# TI_Bluetooth.net
KiCad netlist of a schematic drawn in EAGLE
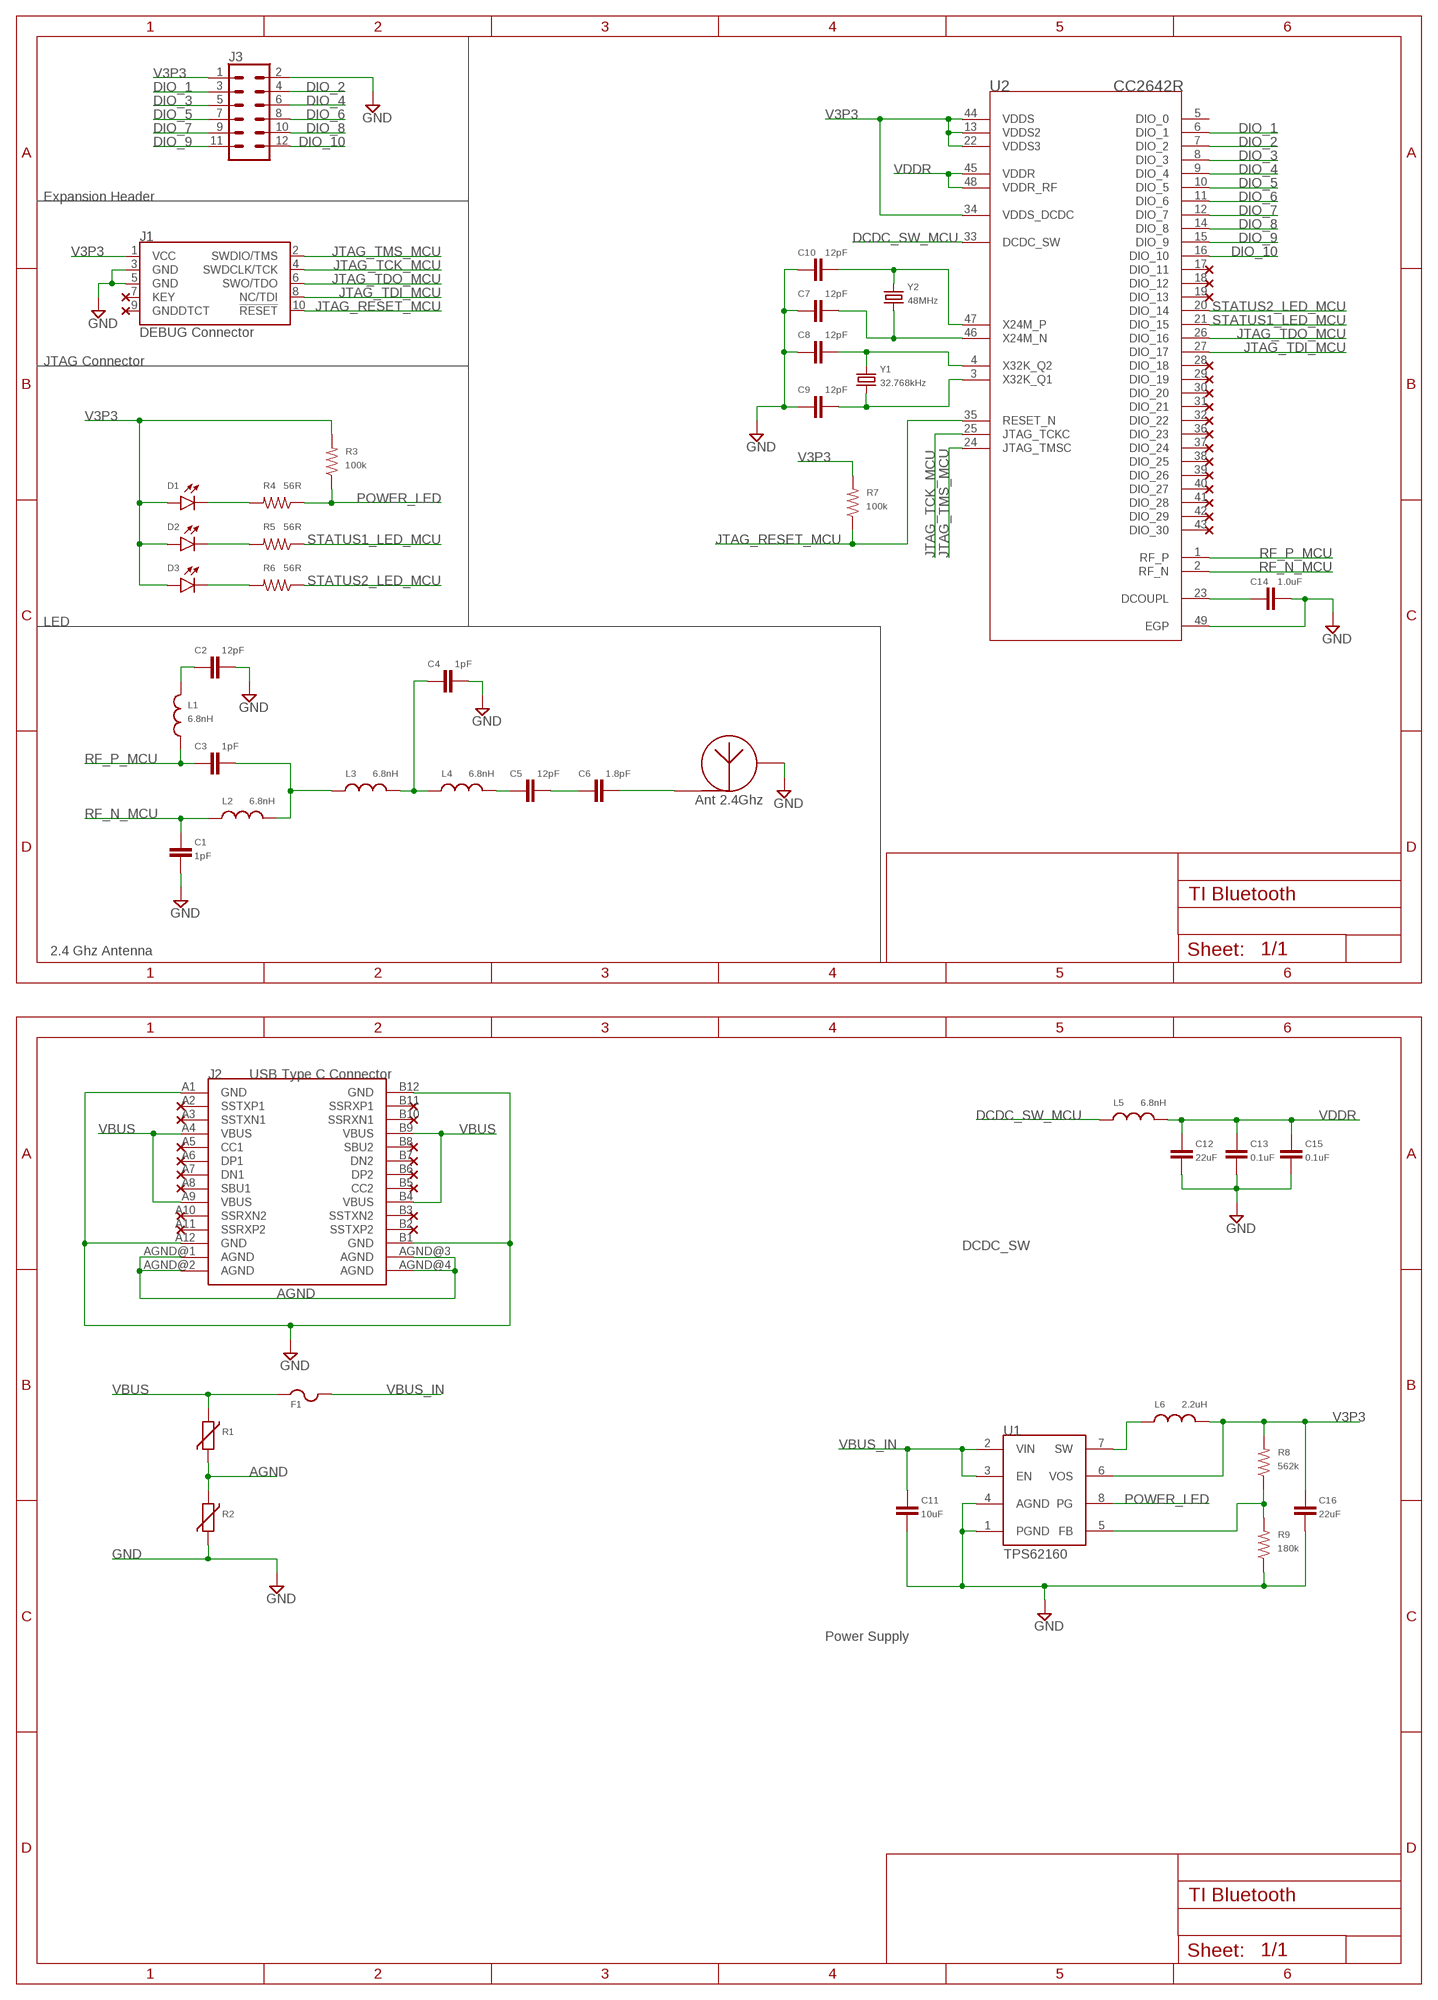
[diagram p0: schematic, sheet 1]

(export (version "E")
  (design (tool "Eeschema 10.0.6"))
  (components
    (comp (ref "ANT1")
      (value "TI_AN043")
      (footprint "eagle-import:TI_AN043")
      (libsource (lib "eagle-import") (part "TI_AN043"))
    )
    (comp (ref "C1")
      (value "1pF")
      (footprint "eagle-import:C0603")
      (libsource (lib "eagle-import") (part "C-EUC0603"))
    )
    (comp (ref "C2")
      (value "12pF")
      (footprint "eagle-import:C0603")
      (libsource (lib "eagle-import") (part "C-EUC0603"))
    )
    (comp (ref "C3")
      (value "1pF")
      (footprint "eagle-import:C0603")
      (libsource (lib "eagle-import") (part "C-EUC0603"))
    )
    (comp (ref "C4")
      (value "1pF")
      (footprint "eagle-import:C0603")
      (libsource (lib "eagle-import") (part "C-EUC0603"))
    )
    (comp (ref "C5")
      (value "12pF")
      (footprint "eagle-import:C0603")
      (libsource (lib "eagle-import") (part "C-EUC0603"))
    )
    (comp (ref "C6")
      (value "1.8pF")
      (footprint "eagle-import:C0603")
      (libsource (lib "eagle-import") (part "C-EUC0603"))
    )
    (comp (ref "C7")
      (value "12pF")
      (footprint "eagle-import:C0603")
      (libsource (lib "eagle-import") (part "C-EUC0603"))
    )
    (comp (ref "C8")
      (value "12pF")
      (footprint "eagle-import:C0603")
      (libsource (lib "eagle-import") (part "C-EUC0603"))
    )
    (comp (ref "C9")
      (value "12pF")
      (footprint "eagle-import:C0603")
      (libsource (lib "eagle-import") (part "C-EUC0603"))
    )
    (comp (ref "C10")
      (value "12pF")
      (footprint "eagle-import:C0603")
      (libsource (lib "eagle-import") (part "C-EUC0603"))
    )
    (comp (ref "C11")
      (value "10uF")
      (footprint "eagle-import:C0603")
      (libsource (lib "eagle-import") (part "C-EUC0603"))
    )
    (comp (ref "C12")
      (value "22uF")
      (footprint "eagle-import:C0603")
      (libsource (lib "eagle-import") (part "C-EUC0603"))
    )
    (comp (ref "C13")
      (value "0.1uF")
      (footprint "eagle-import:C0603")
      (libsource (lib "eagle-import") (part "C-EUC0603"))
    )
    (comp (ref "C14")
      (value "1.0uF")
      (footprint "eagle-import:C0603")
      (libsource (lib "eagle-import") (part "C-EUC0603"))
    )
    (comp (ref "C15")
      (value "0.1uF")
      (footprint "eagle-import:C0603")
      (libsource (lib "eagle-import") (part "C-EUC0603"))
    )
    (comp (ref "C16")
      (value "22uF")
      (footprint "eagle-import:C0603")
      (libsource (lib "eagle-import") (part "C-EUC0603"))
    )
    (comp (ref "D1")
      (value "POWER")
      (footprint "eagle-import:LED-1206")
      (libsource (lib "eagle-import") (part "LED1206"))
    )
    (comp (ref "D2")
      (value "STATUS1")
      (footprint "eagle-import:LED-1206")
      (libsource (lib "eagle-import") (part "LED1206"))
    )
    (comp (ref "D3")
      (value "STATUS2")
      (footprint "eagle-import:LED-1206")
      (libsource (lib "eagle-import") (part "LED1206"))
    )
    (comp (ref "F1")
      (value "1206L110THYR")
      (footprint "eagle-import:R1206")
      (libsource (lib "eagle-import") (part "PTCFUSE-1206"))
    )
    (comp (ref "J1")
      (value "DEBUG Connector")
      (footprint "eagle-import:SAMTECH_FTSH-105-01")
      (libsource (lib "eagle-import") (part "CORTEX_DEBUG_SMD"))
    )
    (comp (ref "J2")
      (value "USB Type C Connector")
      (footprint "eagle-import:USB-C31-S-RA-CS1-BK-TR")
      (libsource (lib "eagle-import") (part "USB-C31-S-RA-CS1-BK-TR"))
    )
    (comp (ref "J3")
      (value "Expansion Header")
      (footprint "eagle-import:2X6")
      (libsource (lib "eagle-import") (part "CONN_06X2PTH_FEMALE"))
    )
    (comp (ref "L1")
      (value "6.8nH")
      (footprint "eagle-import:INDC1608X95N")
      (libsource (lib "eagle-import") (part "LCHIP-0603(1608-METRIC)_"))
    )
    (comp (ref "L2")
      (value "6.8nH")
      (footprint "eagle-import:INDC1608X95N")
      (libsource (lib "eagle-import") (part "LCHIP-0603(1608-METRIC)_"))
    )
    (comp (ref "L3")
      (value "6.8nH")
      (footprint "eagle-import:INDC1608X95N")
      (libsource (lib "eagle-import") (part "LCHIP-0603(1608-METRIC)_"))
    )
    (comp (ref "L4")
      (value "6.8nH")
      (footprint "eagle-import:INDC1608X95N")
      (libsource (lib "eagle-import") (part "LCHIP-0603(1608-METRIC)_"))
    )
    (comp (ref "L5")
      (value "6.8nH")
      (footprint "eagle-import:INDC1608X95N")
      (libsource (lib "eagle-import") (part "LCHIP-0603(1608-METRIC)_"))
    )
    (comp (ref "L6")
      (value "2.2uH")
      (footprint "eagle-import:INDC1608X95N")
      (libsource (lib "eagle-import") (part "LCHIP-0603(1608-METRIC)_"))
    )
    (comp (ref "R1")
      (value "V5.5MLA")
      (footprint "eagle-import:CT_CN0603")
      (libsource (lib "eagle-import") (part "VARISTORCN0603"))
    )
    (comp (ref "R2")
      (value "V5.5MLA")
      (footprint "eagle-import:CT_CN0603")
      (libsource (lib "eagle-import") (part "VARISTORCN0603"))
    )
    (comp (ref "R3")
      (value "100k")
      (footprint "eagle-import:R0603")
      (libsource (lib "eagle-import") (part "R-US_R0603"))
    )
    (comp (ref "R4")
      (value "56R")
      (footprint "eagle-import:R0603")
      (libsource (lib "eagle-import") (part "R-US_R0603"))
    )
    (comp (ref "R5")
      (value "56R")
      (footprint "eagle-import:R0603")
      (libsource (lib "eagle-import") (part "R-US_R0603"))
    )
    (comp (ref "R6")
      (value "56R")
      (footprint "eagle-import:R0603")
      (libsource (lib "eagle-import") (part "R-US_R0603"))
    )
    (comp (ref "R7")
      (value "100k")
      (footprint "eagle-import:R0603")
      (libsource (lib "eagle-import") (part "R-US_R0603"))
    )
    (comp (ref "R8")
      (value "562k")
      (footprint "eagle-import:R0603")
      (libsource (lib "eagle-import") (part "R-US_R0603"))
    )
    (comp (ref "R9")
      (value "180k")
      (footprint "eagle-import:R0603")
      (libsource (lib "eagle-import") (part "R-US_R0603"))
    )
    (comp (ref "U1")
      (value "TPS62160")
      (footprint "eagle-import:SOP65P490X110-8N")
      (libsource (lib "eagle-import") (part "TPS62160VSSOP"))
    )
    (comp (ref "U2")
      (value "CC2642R")
      (footprint "eagle-import:QFN50P700X690X100-49T515N")
      (libsource (lib "eagle-import") (part "CC2642R1FRGZRRGZ0048A"))
    )
    (comp (ref "Y1")
      (value "32.768kHz")
      (footprint "eagle-import:CRYSTAL-PTH-2X6-CYL")
      (libsource (lib "eagle-import") (part "CRYSTAL-32.768KHZPTH-2X6"))
    )
    (comp (ref "Y2")
      (value "48MHz")
      (footprint "eagle-import:CRYSTAL-SMD-5X3.2-2PAD")
      (libsource (lib "eagle-import") (part "CRYSTALSMD-5X3.2-2PAD"))
    )
  )
  (nets
    (net (code "1") (name "/AGND") (class "Default")
      (node (ref "J2") (pin "AGND@1") (pinfunction "AGND_AGND@1") (pintype "bidirectional"))
      (node (ref "J2") (pin "AGND@2") (pinfunction "AGND_AGND@2") (pintype "bidirectional"))
      (node (ref "J2") (pin "AGND@3") (pinfunction "AGND_AGND@3") (pintype "bidirectional"))
      (node (ref "J2") (pin "AGND@4") (pinfunction "AGND_AGND@4") (pintype "bidirectional"))
      (node (ref "R1") (pin "2") (pinfunction "2_2") (pintype "passive"))
      (node (ref "R2") (pin "1") (pinfunction "1_1") (pintype "passive"))
    )
    (net (code "2") (name "/DCDC_SW_MCU") (class "Default")
      (node (ref "L5") (pin "1") (pinfunction "1_1") (pintype "passive"))
      (node (ref "U2") (pin "33") (pinfunction "DCDC_SW_33") (pintype "power_in"))
    )
    (net (code "3") (name "/DIO_1") (class "Default")
      (node (ref "J3") (pin "3") (pinfunction "3_3") (pintype "passive"))
      (node (ref "U2") (pin "6") (pinfunction "DIO_1_6") (pintype "bidirectional"))
    )
    (net (code "4") (name "/DIO_2") (class "Default")
      (node (ref "J3") (pin "4") (pinfunction "4_4") (pintype "passive"))
      (node (ref "U2") (pin "7") (pinfunction "DIO_2_7") (pintype "bidirectional"))
    )
    (net (code "5") (name "/DIO_3") (class "Default")
      (node (ref "J3") (pin "5") (pinfunction "5_5") (pintype "passive"))
      (node (ref "U2") (pin "8") (pinfunction "DIO_3_8") (pintype "bidirectional"))
    )
    (net (code "6") (name "/DIO_4") (class "Default")
      (node (ref "J3") (pin "6") (pinfunction "6_6") (pintype "passive"))
      (node (ref "U2") (pin "9") (pinfunction "DIO_4_9") (pintype "bidirectional"))
    )
    (net (code "7") (name "/DIO_5") (class "Default")
      (node (ref "J3") (pin "7") (pinfunction "7_7") (pintype "passive"))
      (node (ref "U2") (pin "10") (pinfunction "DIO_5_10") (pintype "bidirectional"))
    )
    (net (code "8") (name "/DIO_6") (class "Default")
      (node (ref "J3") (pin "8") (pinfunction "8_8") (pintype "passive"))
      (node (ref "U2") (pin "11") (pinfunction "DIO_6_11") (pintype "bidirectional"))
    )
    (net (code "9") (name "/DIO_7") (class "Default")
      (node (ref "J3") (pin "9") (pinfunction "9_9") (pintype "passive"))
      (node (ref "U2") (pin "12") (pinfunction "DIO_7_12") (pintype "bidirectional"))
    )
    (net (code "10") (name "/DIO_8") (class "Default")
      (node (ref "J3") (pin "10") (pinfunction "10_10") (pintype "passive"))
      (node (ref "U2") (pin "14") (pinfunction "DIO_8_14") (pintype "bidirectional"))
    )
    (net (code "11") (name "/DIO_9") (class "Default")
      (node (ref "J3") (pin "11") (pinfunction "11_11") (pintype "passive"))
      (node (ref "U2") (pin "15") (pinfunction "DIO_9_15") (pintype "bidirectional"))
    )
    (net (code "12") (name "/DIO_10") (class "Default")
      (node (ref "J3") (pin "12") (pinfunction "12_12") (pintype "passive"))
      (node (ref "U2") (pin "16") (pinfunction "DIO_10_16") (pintype "bidirectional"))
    )
    (net (code "13") (name "/JTAG_RESET_MCU") (class "Default")
      (node (ref "J1") (pin "10") (pinfunction "~{RESET}_10") (pintype "bidirectional"))
      (node (ref "R7") (pin "1") (pinfunction "1_1") (pintype "passive"))
      (node (ref "U2") (pin "35") (pinfunction "RESET_N_35") (pintype "input"))
    )
    (net (code "14") (name "/JTAG_TCK_MCU") (class "Default")
      (node (ref "J1") (pin "4") (pinfunction "SWDCLK/TCK_4") (pintype "bidirectional"))
      (node (ref "U2") (pin "25") (pinfunction "JTAG_TCKC_25") (pintype "bidirectional"))
    )
    (net (code "15") (name "/JTAG_TDI_MCU") (class "Default")
      (node (ref "J1") (pin "8") (pinfunction "NC/TDI_8") (pintype "bidirectional"))
      (node (ref "U2") (pin "27") (pinfunction "DIO_17_27") (pintype "bidirectional"))
    )
    (net (code "16") (name "/JTAG_TDO_MCU") (class "Default")
      (node (ref "J1") (pin "6") (pinfunction "SWO/TDO_6") (pintype "bidirectional"))
      (node (ref "U2") (pin "26") (pinfunction "DIO_16_26") (pintype "bidirectional"))
    )
    (net (code "17") (name "/JTAG_TMS_MCU") (class "Default")
      (node (ref "J1") (pin "2") (pinfunction "SWDIO/TMS_2") (pintype "bidirectional"))
      (node (ref "U2") (pin "24") (pinfunction "JTAG_TMSC_24") (pintype "bidirectional"))
    )
    (net (code "18") (name "/POWER_LED") (class "Default")
      (node (ref "R3") (pin "1") (pinfunction "1_1") (pintype "passive"))
      (node (ref "R4") (pin "1") (pinfunction "1_1") (pintype "passive"))
      (node (ref "U1") (pin "8") (pinfunction "PG_8") (pintype "bidirectional"))
    )
    (net (code "19") (name "/RF_N_MCU") (class "Default")
      (node (ref "C1") (pin "1") (pinfunction "1_1") (pintype "passive"))
      (node (ref "L2") (pin "1") (pinfunction "1_1") (pintype "passive"))
      (node (ref "U2") (pin "2") (pinfunction "RF_N_2") (pintype "bidirectional"))
    )
    (net (code "20") (name "/RF_P_MCU") (class "Default")
      (node (ref "C3") (pin "1") (pinfunction "1_1") (pintype "passive"))
      (node (ref "L1") (pin "1") (pinfunction "1_1") (pintype "passive"))
      (node (ref "U2") (pin "1") (pinfunction "RF_P_1") (pintype "bidirectional"))
    )
    (net (code "21") (name "/STATUS1_LED_MCU") (class "Default")
      (node (ref "R5") (pin "1") (pinfunction "1_1") (pintype "passive"))
      (node (ref "U2") (pin "21") (pinfunction "DIO_15_21") (pintype "bidirectional"))
    )
    (net (code "22") (name "/STATUS2_LED_MCU") (class "Default")
      (node (ref "R6") (pin "1") (pinfunction "1_1") (pintype "passive"))
      (node (ref "U2") (pin "20") (pinfunction "DIO_14_20") (pintype "bidirectional"))
    )
    (net (code "23") (name "/V3P3") (class "Default")
      (node (ref "C16") (pin "1") (pinfunction "1_1") (pintype "passive"))
      (node (ref "D1") (pin "A") (pinfunction "A_A") (pintype "passive"))
      (node (ref "D2") (pin "A") (pinfunction "A_A") (pintype "passive"))
      (node (ref "D3") (pin "A") (pinfunction "A_A") (pintype "passive"))
      (node (ref "J1") (pin "1") (pinfunction "VCC_1") (pintype "bidirectional"))
      (node (ref "J3") (pin "1") (pinfunction "1_1") (pintype "passive"))
      (node (ref "L6") (pin "2") (pinfunction "2_2") (pintype "passive"))
      (node (ref "R3") (pin "2") (pinfunction "2_2") (pintype "passive"))
      (node (ref "R7") (pin "2") (pinfunction "2_2") (pintype "passive"))
      (node (ref "R8") (pin "2") (pinfunction "2_2") (pintype "passive"))
      (node (ref "U1") (pin "6") (pinfunction "VOS_6") (pintype "bidirectional"))
      (node (ref "U2") (pin "13") (pinfunction "VDDS2_13") (pintype "power_in"))
      (node (ref "U2") (pin "22") (pinfunction "VDDS3_22") (pintype "power_in"))
      (node (ref "U2") (pin "34") (pinfunction "VDDS_DCDC_34") (pintype "power_in"))
      (node (ref "U2") (pin "44") (pinfunction "VDDS_44") (pintype "power_in"))
    )
    (net (code "24") (name "/VBUS") (class "Default")
      (node (ref "F1") (pin "1") (pinfunction "1_1") (pintype "passive"))
      (node (ref "J2") (pin "A4") (pinfunction "VBUS_A4") (pintype "bidirectional"))
      (node (ref "J2") (pin "A9") (pinfunction "VBUS_A9") (pintype "bidirectional"))
      (node (ref "J2") (pin "B4") (pinfunction "VBUS_B4") (pintype "bidirectional"))
      (node (ref "J2") (pin "B9") (pinfunction "VBUS_B9") (pintype "bidirectional"))
      (node (ref "R1") (pin "1") (pinfunction "1_1") (pintype "passive"))
    )
    (net (code "25") (name "/VBUS_IN") (class "Default")
      (node (ref "C11") (pin "1") (pinfunction "1_1") (pintype "passive"))
      (node (ref "F1") (pin "2") (pinfunction "2_2") (pintype "passive"))
      (node (ref "U1") (pin "2") (pinfunction "VIN_2") (pintype "bidirectional"))
      (node (ref "U1") (pin "3") (pinfunction "EN_3") (pintype "bidirectional"))
    )
    (net (code "26") (name "/VDDR") (class "Default")
      (node (ref "C12") (pin "1") (pinfunction "1_1") (pintype "passive"))
      (node (ref "C13") (pin "1") (pinfunction "1_1") (pintype "passive"))
      (node (ref "C15") (pin "1") (pinfunction "1_1") (pintype "passive"))
      (node (ref "L5") (pin "2") (pinfunction "2_2") (pintype "passive"))
      (node (ref "U2") (pin "45") (pinfunction "VDDR_45") (pintype "power_in"))
      (node (ref "U2") (pin "48") (pinfunction "VDDR_RF_48") (pintype "power_in"))
    )
    (net (code "27") (name "GND") (class "Default")
      (node (ref "ANT1") (pin "FEED") (pinfunction "FEED_FEED") (pintype "bidirectional"))
      (node (ref "ANT1") (pin "RETURN") (pinfunction "RETURN_RETURN") (pintype "bidirectional"))
      (node (ref "C1") (pin "2") (pinfunction "2_2") (pintype "passive"))
      (node (ref "C10") (pin "2") (pinfunction "2_2") (pintype "passive"))
      (node (ref "C11") (pin "2") (pinfunction "2_2") (pintype "passive"))
      (node (ref "C12") (pin "2") (pinfunction "2_2") (pintype "passive"))
      (node (ref "C13") (pin "2") (pinfunction "2_2") (pintype "passive"))
      (node (ref "C14") (pin "2") (pinfunction "2_2") (pintype "passive"))
      (node (ref "C15") (pin "2") (pinfunction "2_2") (pintype "passive"))
      (node (ref "C16") (pin "2") (pinfunction "2_2") (pintype "passive"))
      (node (ref "C2") (pin "2") (pinfunction "2_2") (pintype "passive"))
      (node (ref "C4") (pin "2") (pinfunction "2_2") (pintype "passive"))
      (node (ref "C6") (pin "2") (pinfunction "2_2") (pintype "passive"))
      (node (ref "C7") (pin "1") (pinfunction "1_1") (pintype "passive"))
      (node (ref "C8") (pin "1") (pinfunction "1_1") (pintype "passive"))
      (node (ref "C9") (pin "1") (pinfunction "1_1") (pintype "passive"))
      (node (ref "J1") (pin "3") (pinfunction "GND_3") (pintype "bidirectional"))
      (node (ref "J1") (pin "5") (pinfunction "GND_5") (pintype "bidirectional"))
      (node (ref "J2") (pin "A1") (pinfunction "GND_A1") (pintype "bidirectional"))
      (node (ref "J2") (pin "A12") (pinfunction "GND_A12") (pintype "bidirectional"))
      (node (ref "J2") (pin "B1") (pinfunction "GND_B1") (pintype "bidirectional"))
      (node (ref "J2") (pin "B12") (pinfunction "GND_B12") (pintype "bidirectional"))
      (node (ref "J3") (pin "2") (pinfunction "2_2") (pintype "passive"))
      (node (ref "R2") (pin "2") (pinfunction "2_2") (pintype "passive"))
      (node (ref "R9") (pin "1") (pinfunction "1_1") (pintype "passive"))
      (node (ref "U1") (pin "1") (pinfunction "PGND_1") (pintype "bidirectional"))
      (node (ref "U1") (pin "4") (pinfunction "AGND_4") (pintype "bidirectional"))
      (node (ref "U2") (pin "49") (pinfunction "EGP_49") (pintype "power_in"))
    )
    (net (code "28") (name "Net-(C2-Pad1)") (class "Default")
      (node (ref "C2") (pin "1") (pinfunction "1_1") (pintype "passive"))
      (node (ref "L1") (pin "2") (pinfunction "2_2") (pintype "passive"))
    )
    (net (code "29") (name "Net-(C3-Pad2)") (class "Default")
      (node (ref "C3") (pin "2") (pinfunction "2_2") (pintype "passive"))
      (node (ref "L2") (pin "2") (pinfunction "2_2") (pintype "passive"))
      (node (ref "L3") (pin "1") (pinfunction "1_1") (pintype "passive"))
    )
    (net (code "30") (name "Net-(C4-Pad1)") (class "Default")
      (node (ref "C4") (pin "1") (pinfunction "1_1") (pintype "passive"))
      (node (ref "L3") (pin "2") (pinfunction "2_2") (pintype "passive"))
      (node (ref "L4") (pin "1") (pinfunction "1_1") (pintype "passive"))
    )
    (net (code "31") (name "Net-(C5-Pad1)") (class "Default")
      (node (ref "C5") (pin "1") (pinfunction "1_1") (pintype "passive"))
      (node (ref "L4") (pin "2") (pinfunction "2_2") (pintype "passive"))
    )
    (net (code "32") (name "Net-(C5-Pad2)") (class "Default")
      (node (ref "C5") (pin "2") (pinfunction "2_2") (pintype "passive"))
      (node (ref "C6") (pin "1") (pinfunction "1_1") (pintype "passive"))
    )
    (net (code "33") (name "Net-(D1-PadC)") (class "Default")
      (node (ref "D1") (pin "C") (pinfunction "C_C") (pintype "passive"))
      (node (ref "R4") (pin "2") (pinfunction "2_2") (pintype "passive"))
    )
    (net (code "34") (name "Net-(D2-PadC)") (class "Default")
      (node (ref "D2") (pin "C") (pinfunction "C_C") (pintype "passive"))
      (node (ref "R5") (pin "2") (pinfunction "2_2") (pintype "passive"))
    )
    (net (code "35") (name "Net-(D3-PadC)") (class "Default")
      (node (ref "D3") (pin "C") (pinfunction "C_C") (pintype "passive"))
      (node (ref "R6") (pin "2") (pinfunction "2_2") (pintype "passive"))
    )
    (net (code "36") (name "Net-(U1-FB)") (class "Default")
      (node (ref "R8") (pin "1") (pinfunction "1_1") (pintype "passive"))
      (node (ref "R9") (pin "2") (pinfunction "2_2") (pintype "passive"))
      (node (ref "U1") (pin "5") (pinfunction "FB_5") (pintype "bidirectional"))
    )
    (net (code "37") (name "Net-(U1-SW)") (class "Default")
      (node (ref "L6") (pin "1") (pinfunction "1_1") (pintype "passive"))
      (node (ref "U1") (pin "7") (pinfunction "SW_7") (pintype "bidirectional"))
    )
    (net (code "38") (name "Net-(U2-DCOUPL)") (class "Default")
      (node (ref "C14") (pin "1") (pinfunction "1_1") (pintype "passive"))
      (node (ref "U2") (pin "23") (pinfunction "DCOUPL_23") (pintype "power_in"))
    )
    (net (code "39") (name "Net-(U2-X24M_N)") (class "Default")
      (node (ref "C7") (pin "2") (pinfunction "2_2") (pintype "passive"))
      (node (ref "U2") (pin "46") (pinfunction "X24M_N_46") (pintype "bidirectional"))
      (node (ref "Y2") (pin "P$1") (pinfunction "1_P$1") (pintype "passive"))
    )
    (net (code "40") (name "Net-(U2-X24M_P)") (class "Default")
      (node (ref "C10") (pin "1") (pinfunction "1_1") (pintype "passive"))
      (node (ref "U2") (pin "47") (pinfunction "X24M_P_47") (pintype "bidirectional"))
      (node (ref "Y2") (pin "P$2") (pinfunction "2_P$2") (pintype "passive"))
    )
    (net (code "41") (name "Net-(U2-X32K_Q1)") (class "Default")
      (node (ref "C9") (pin "2") (pinfunction "2_2") (pintype "passive"))
      (node (ref "U2") (pin "3") (pinfunction "X32K_Q1_3") (pintype "bidirectional"))
      (node (ref "Y1") (pin "2") (pinfunction "2_2") (pintype "passive"))
    )
    (net (code "42") (name "Net-(U2-X32K_Q2)") (class "Default")
      (node (ref "C8") (pin "2") (pinfunction "2_2") (pintype "passive"))
      (node (ref "U2") (pin "4") (pinfunction "X32K_Q2_4") (pintype "bidirectional"))
      (node (ref "Y1") (pin "1") (pinfunction "1_1") (pintype "passive"))
    )
    (net (code "43") (name "unconnected-(J1-GNDDTCT-Pad9)") (class "Default")
      (node (ref "J1") (pin "9") (pinfunction "GNDDTCT_9") (pintype "bidirectional"))
    )
    (net (code "44") (name "unconnected-(J1-KEY-Pad7)") (class "Default")
      (node (ref "J1") (pin "7") (pinfunction "KEY_7") (pintype "bidirectional"))
    )
    (net (code "45") (name "unconnected-(J2-CC1-PadA5)") (class "Default")
      (node (ref "J2") (pin "A5") (pinfunction "CC1_A5") (pintype "bidirectional"))
    )
    (net (code "46") (name "unconnected-(J2-CC2-PadB5)") (class "Default")
      (node (ref "J2") (pin "B5") (pinfunction "CC2_B5") (pintype "bidirectional"))
    )
    (net (code "47") (name "unconnected-(J2-DN1-PadA7)") (class "Default")
      (node (ref "J2") (pin "A7") (pinfunction "DN1_A7") (pintype "bidirectional"))
    )
    (net (code "48") (name "unconnected-(J2-DN2-PadB7)") (class "Default")
      (node (ref "J2") (pin "B7") (pinfunction "DN2_B7") (pintype "bidirectional"))
    )
    (net (code "49") (name "unconnected-(J2-DP1-PadA6)") (class "Default")
      (node (ref "J2") (pin "A6") (pinfunction "DP1_A6") (pintype "bidirectional"))
    )
    (net (code "50") (name "unconnected-(J2-DP2-PadB6)") (class "Default")
      (node (ref "J2") (pin "B6") (pinfunction "DP2_B6") (pintype "bidirectional"))
    )
    (net (code "51") (name "unconnected-(J2-SBU1-PadA8)") (class "Default")
      (node (ref "J2") (pin "A8") (pinfunction "SBU1_A8") (pintype "bidirectional"))
    )
    (net (code "52") (name "unconnected-(J2-SBU2-PadB8)") (class "Default")
      (node (ref "J2") (pin "B8") (pinfunction "SBU2_B8") (pintype "bidirectional"))
    )
    (net (code "53") (name "unconnected-(J2-SSRXN1-PadB10)") (class "Default")
      (node (ref "J2") (pin "B10") (pinfunction "SSRXN1_B10") (pintype "bidirectional"))
    )
    (net (code "54") (name "unconnected-(J2-SSRXN2-PadA10)") (class "Default")
      (node (ref "J2") (pin "A10") (pinfunction "SSRXN2_A10") (pintype "bidirectional"))
    )
    (net (code "55") (name "unconnected-(J2-SSRXP1-PadB11)") (class "Default")
      (node (ref "J2") (pin "B11") (pinfunction "SSRXP1_B11") (pintype "bidirectional"))
    )
    (net (code "56") (name "unconnected-(J2-SSRXP2-PadA11)") (class "Default")
      (node (ref "J2") (pin "A11") (pinfunction "SSRXP2_A11") (pintype "bidirectional"))
    )
    (net (code "57") (name "unconnected-(J2-SSTXN1-PadA3)") (class "Default")
      (node (ref "J2") (pin "A3") (pinfunction "SSTXN1_A3") (pintype "bidirectional"))
    )
    (net (code "58") (name "unconnected-(J2-SSTXN2-PadB3)") (class "Default")
      (node (ref "J2") (pin "B3") (pinfunction "SSTXN2_B3") (pintype "bidirectional"))
    )
    (net (code "59") (name "unconnected-(J2-SSTXP1-PadA2)") (class "Default")
      (node (ref "J2") (pin "A2") (pinfunction "SSTXP1_A2") (pintype "bidirectional"))
    )
    (net (code "60") (name "unconnected-(J2-SSTXP2-PadB2)") (class "Default")
      (node (ref "J2") (pin "B2") (pinfunction "SSTXP2_B2") (pintype "bidirectional"))
    )
    (net (code "61") (name "unconnected-(U2-DIO_0-Pad5)") (class "Default")
      (node (ref "U2") (pin "5") (pinfunction "DIO_0_5") (pintype "bidirectional"))
    )
    (net (code "62") (name "unconnected-(U2-DIO_11-Pad17)") (class "Default")
      (node (ref "U2") (pin "17") (pinfunction "DIO_11_17") (pintype "bidirectional"))
    )
    (net (code "63") (name "unconnected-(U2-DIO_12-Pad18)") (class "Default")
      (node (ref "U2") (pin "18") (pinfunction "DIO_12_18") (pintype "bidirectional"))
    )
    (net (code "64") (name "unconnected-(U2-DIO_13-Pad19)") (class "Default")
      (node (ref "U2") (pin "19") (pinfunction "DIO_13_19") (pintype "bidirectional"))
    )
    (net (code "65") (name "unconnected-(U2-DIO_18-Pad28)") (class "Default")
      (node (ref "U2") (pin "28") (pinfunction "DIO_18_28") (pintype "bidirectional"))
    )
    (net (code "66") (name "unconnected-(U2-DIO_19-Pad29)") (class "Default")
      (node (ref "U2") (pin "29") (pinfunction "DIO_19_29") (pintype "bidirectional"))
    )
    (net (code "67") (name "unconnected-(U2-DIO_20-Pad30)") (class "Default")
      (node (ref "U2") (pin "30") (pinfunction "DIO_20_30") (pintype "bidirectional"))
    )
    (net (code "68") (name "unconnected-(U2-DIO_21-Pad31)") (class "Default")
      (node (ref "U2") (pin "31") (pinfunction "DIO_21_31") (pintype "bidirectional"))
    )
    (net (code "69") (name "unconnected-(U2-DIO_22-Pad32)") (class "Default")
      (node (ref "U2") (pin "32") (pinfunction "DIO_22_32") (pintype "bidirectional"))
    )
    (net (code "70") (name "unconnected-(U2-DIO_23-Pad36)") (class "Default")
      (node (ref "U2") (pin "36") (pinfunction "DIO_23_36") (pintype "bidirectional"))
    )
    (net (code "71") (name "unconnected-(U2-DIO_24-Pad37)") (class "Default")
      (node (ref "U2") (pin "37") (pinfunction "DIO_24_37") (pintype "bidirectional"))
    )
    (net (code "72") (name "unconnected-(U2-DIO_25-Pad38)") (class "Default")
      (node (ref "U2") (pin "38") (pinfunction "DIO_25_38") (pintype "bidirectional"))
    )
    (net (code "73") (name "unconnected-(U2-DIO_26-Pad39)") (class "Default")
      (node (ref "U2") (pin "39") (pinfunction "DIO_26_39") (pintype "bidirectional"))
    )
    (net (code "74") (name "unconnected-(U2-DIO_27-Pad40)") (class "Default")
      (node (ref "U2") (pin "40") (pinfunction "DIO_27_40") (pintype "bidirectional"))
    )
    (net (code "75") (name "unconnected-(U2-DIO_28-Pad41)") (class "Default")
      (node (ref "U2") (pin "41") (pinfunction "DIO_28_41") (pintype "bidirectional"))
    )
    (net (code "76") (name "unconnected-(U2-DIO_29-Pad42)") (class "Default")
      (node (ref "U2") (pin "42") (pinfunction "DIO_29_42") (pintype "bidirectional"))
    )
    (net (code "77") (name "unconnected-(U2-DIO_30-Pad43)") (class "Default")
      (node (ref "U2") (pin "43") (pinfunction "DIO_30_43") (pintype "bidirectional"))
    )
  )
)
